# mainBoard.net
KiCad netlist of a schematic drawn in EAGLE
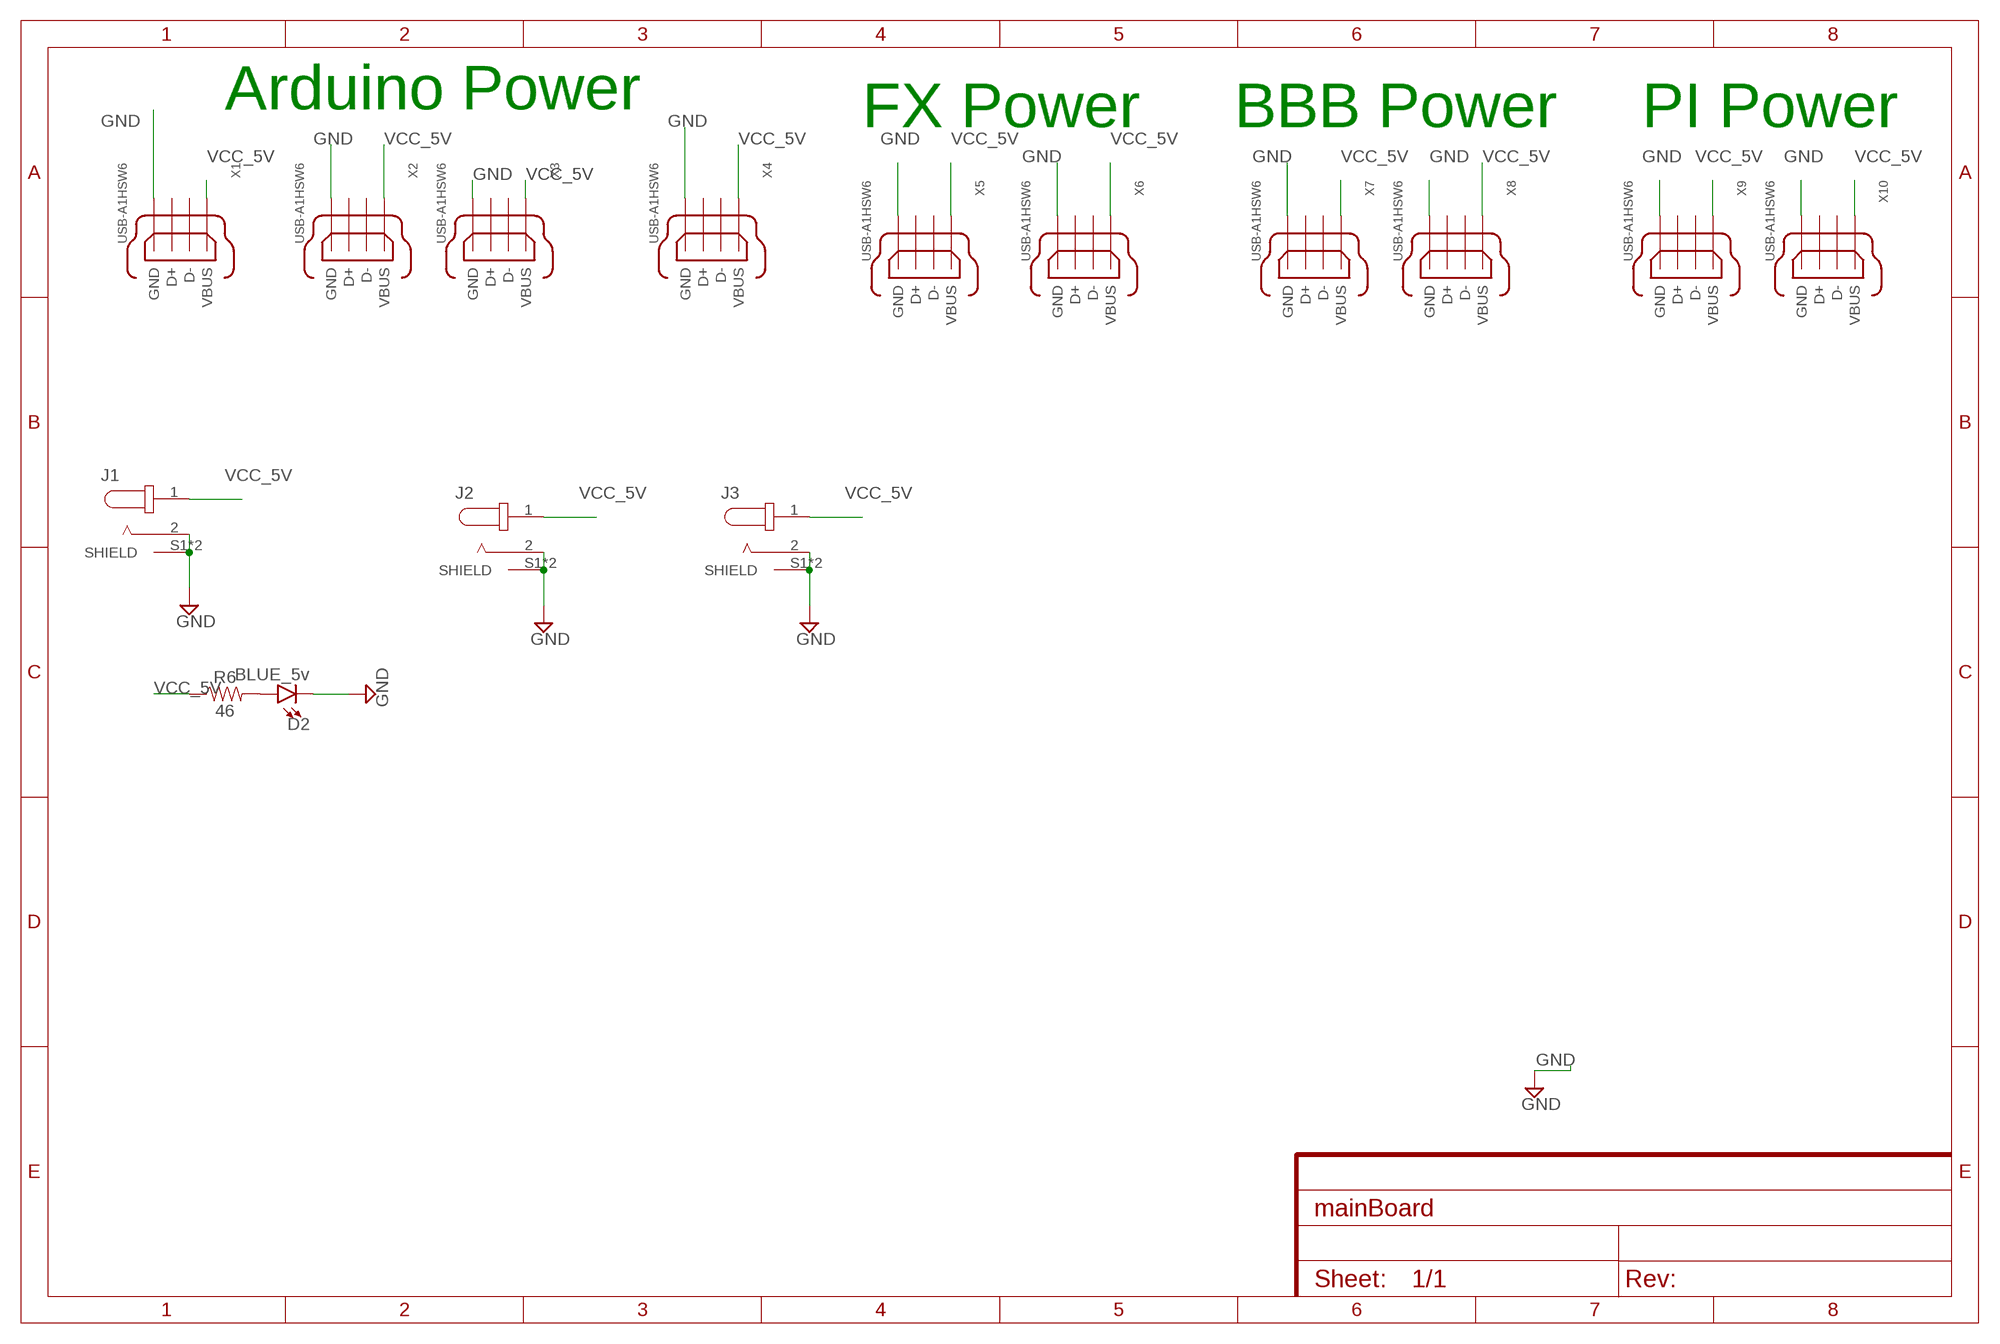
[diagram p0: schematic, sheet 1]

(export (version "E")
  (design (tool "Eeschema 10.0.6"))
  (components
    (comp (ref "D2")
      (value "BLUE_5v")
      (footprint "eagle-import:LED-0603")
      (libsource (lib "eagle-import") (part "LED-BLUE0603"))
    )
    (comp (ref "J1")
      (value "PJ-063AH")
      (footprint "eagle-import:CUI_PJ-063AH")
      (fields (field (name "MF") "CUI Inc."))
      (libsource (lib "eagle-import") (part "PJ-063AH"))
    )
    (comp (ref "J2")
      (value "PJ-063AH")
      (footprint "eagle-import:CUI_PJ-063AH")
      (fields (field (name "MF") "CUI Inc."))
      (libsource (lib "eagle-import") (part "PJ-063AH"))
    )
    (comp (ref "J3")
      (value "PJ-063AH")
      (footprint "eagle-import:CUI_PJ-063AH")
      (fields (field (name "MF") "CUI Inc."))
      (libsource (lib "eagle-import") (part "PJ-063AH"))
    )
    (comp (ref "R6")
      (value "46")
      (footprint "eagle-import:0603")
      (libsource (lib "eagle-import") (part "RESISTOR0603"))
    )
    (comp (ref "X1")
      (value "USB-A1HSW6")
      (footprint "eagle-import:OST_USB-A1HSW6")
      (fields (field (name "MF") "On Shore"))
      (libsource (lib "eagle-import") (part "USB-A1HSW6"))
    )
    (comp (ref "X2")
      (value "USB-A1HSW6")
      (footprint "eagle-import:OST_USB-A1HSW6")
      (fields (field (name "MF") "On Shore"))
      (libsource (lib "eagle-import") (part "USB-A1HSW6"))
    )
    (comp (ref "X3")
      (value "USB-A1HSW6")
      (footprint "eagle-import:OST_USB-A1HSW6")
      (fields (field (name "MF") "On Shore"))
      (libsource (lib "eagle-import") (part "USB-A1HSW6"))
    )
    (comp (ref "X4")
      (value "USB-A1HSW6")
      (footprint "eagle-import:OST_USB-A1HSW6")
      (fields (field (name "MF") "On Shore"))
      (libsource (lib "eagle-import") (part "USB-A1HSW6"))
    )
    (comp (ref "X5")
      (value "USB-A1HSW6")
      (footprint "eagle-import:OST_USB-A1HSW6")
      (fields (field (name "MF") "On Shore"))
      (libsource (lib "eagle-import") (part "USB-A1HSW6"))
    )
    (comp (ref "X6")
      (value "USB-A1HSW6")
      (footprint "eagle-import:OST_USB-A1HSW6")
      (fields (field (name "MF") "On Shore"))
      (libsource (lib "eagle-import") (part "USB-A1HSW6"))
    )
    (comp (ref "X7")
      (value "USB-A1HSW6")
      (footprint "eagle-import:OST_USB-A1HSW6")
      (fields (field (name "MF") "On Shore"))
      (libsource (lib "eagle-import") (part "USB-A1HSW6"))
    )
    (comp (ref "X8")
      (value "USB-A1HSW6")
      (footprint "eagle-import:OST_USB-A1HSW6")
      (fields (field (name "MF") "On Shore"))
      (libsource (lib "eagle-import") (part "USB-A1HSW6"))
    )
    (comp (ref "X9")
      (value "USB-A1HSW6")
      (footprint "eagle-import:OST_USB-A1HSW6")
      (fields (field (name "MF") "On Shore"))
      (libsource (lib "eagle-import") (part "USB-A1HSW6"))
    )
    (comp (ref "X10")
      (value "USB-A1HSW6")
      (footprint "eagle-import:OST_USB-A1HSW6")
      (fields (field (name "MF") "On Shore"))
      (libsource (lib "eagle-import") (part "USB-A1HSW6"))
    )
  )
  (nets
    (net (code "1") (name "/VCC_5V") (class "Default")
      (node (ref "J1") (pin "1") (pinfunction "1_1") (pintype "passive"))
      (node (ref "J2") (pin "1") (pinfunction "1_1") (pintype "passive"))
      (node (ref "J3") (pin "1") (pinfunction "1_1") (pintype "passive"))
      (node (ref "R6") (pin "1") (pinfunction "1_1") (pintype "passive"))
      (node (ref "X1") (pin "1") (pinfunction "VBUS_1") (pintype "power_in"))
      (node (ref "X10") (pin "1") (pinfunction "VBUS_1") (pintype "power_in"))
      (node (ref "X2") (pin "1") (pinfunction "VBUS_1") (pintype "power_in"))
      (node (ref "X3") (pin "1") (pinfunction "VBUS_1") (pintype "power_in"))
      (node (ref "X4") (pin "1") (pinfunction "VBUS_1") (pintype "power_in"))
      (node (ref "X5") (pin "1") (pinfunction "VBUS_1") (pintype "power_in"))
      (node (ref "X6") (pin "1") (pinfunction "VBUS_1") (pintype "power_in"))
      (node (ref "X7") (pin "1") (pinfunction "VBUS_1") (pintype "power_in"))
      (node (ref "X8") (pin "1") (pinfunction "VBUS_1") (pintype "power_in"))
      (node (ref "X9") (pin "1") (pinfunction "VBUS_1") (pintype "power_in"))
    )
    (net (code "2") (name "GND") (class "Default")
      (node (ref "D2") (pin "C") (pinfunction "C_C") (pintype "passive"))
      (node (ref "J1") (pin "2") (pinfunction "2_2") (pintype "passive"))
      (node (ref "J1") (pin "S1") (pinfunction "SHIELD_S1") (pintype "power_in"))
      (node (ref "J1") (pin "S2") (pinfunction "SHIELD_S2") (pintype "power_in"))
      (node (ref "J2") (pin "2") (pinfunction "2_2") (pintype "passive"))
      (node (ref "J2") (pin "S1") (pinfunction "SHIELD_S1") (pintype "power_in"))
      (node (ref "J2") (pin "S2") (pinfunction "SHIELD_S2") (pintype "power_in"))
      (node (ref "J3") (pin "2") (pinfunction "2_2") (pintype "passive"))
      (node (ref "J3") (pin "S1") (pinfunction "SHIELD_S1") (pintype "power_in"))
      (node (ref "J3") (pin "S2") (pinfunction "SHIELD_S2") (pintype "power_in"))
      (node (ref "X1") (pin "4") (pinfunction "GND_4") (pintype "power_in"))
      (node (ref "X10") (pin "4") (pinfunction "GND_4") (pintype "power_in"))
      (node (ref "X2") (pin "4") (pinfunction "GND_4") (pintype "power_in"))
      (node (ref "X3") (pin "4") (pinfunction "GND_4") (pintype "power_in"))
      (node (ref "X4") (pin "4") (pinfunction "GND_4") (pintype "power_in"))
      (node (ref "X5") (pin "4") (pinfunction "GND_4") (pintype "power_in"))
      (node (ref "X6") (pin "4") (pinfunction "GND_4") (pintype "power_in"))
      (node (ref "X7") (pin "4") (pinfunction "GND_4") (pintype "power_in"))
      (node (ref "X8") (pin "4") (pinfunction "GND_4") (pintype "power_in"))
      (node (ref "X9") (pin "4") (pinfunction "GND_4") (pintype "power_in"))
    )
    (net (code "3") (name "Net-(D2-PadA)") (class "Default")
      (node (ref "D2") (pin "A") (pinfunction "A_A") (pintype "passive"))
      (node (ref "R6") (pin "2") (pinfunction "2_2") (pintype "passive"))
    )
    (net (code "4") (name "unconnected-(X1-D+-Pad3)") (class "Default")
      (node (ref "X1") (pin "3") (pinfunction "D+_3") (pintype "bidirectional"))
    )
    (net (code "5") (name "unconnected-(X1-D--Pad2)") (class "Default")
      (node (ref "X1") (pin "2") (pinfunction "D-_2") (pintype "bidirectional"))
    )
    (net (code "6") (name "unconnected-(X2-D+-Pad3)") (class "Default")
      (node (ref "X2") (pin "3") (pinfunction "D+_3") (pintype "bidirectional"))
    )
    (net (code "7") (name "unconnected-(X2-D--Pad2)") (class "Default")
      (node (ref "X2") (pin "2") (pinfunction "D-_2") (pintype "bidirectional"))
    )
    (net (code "8") (name "unconnected-(X3-D+-Pad3)") (class "Default")
      (node (ref "X3") (pin "3") (pinfunction "D+_3") (pintype "bidirectional"))
    )
    (net (code "9") (name "unconnected-(X3-D--Pad2)") (class "Default")
      (node (ref "X3") (pin "2") (pinfunction "D-_2") (pintype "bidirectional"))
    )
    (net (code "10") (name "unconnected-(X4-D+-Pad3)") (class "Default")
      (node (ref "X4") (pin "3") (pinfunction "D+_3") (pintype "bidirectional"))
    )
    (net (code "11") (name "unconnected-(X4-D--Pad2)") (class "Default")
      (node (ref "X4") (pin "2") (pinfunction "D-_2") (pintype "bidirectional"))
    )
    (net (code "12") (name "unconnected-(X5-D+-Pad3)") (class "Default")
      (node (ref "X5") (pin "3") (pinfunction "D+_3") (pintype "bidirectional"))
    )
    (net (code "13") (name "unconnected-(X5-D--Pad2)") (class "Default")
      (node (ref "X5") (pin "2") (pinfunction "D-_2") (pintype "bidirectional"))
    )
    (net (code "14") (name "unconnected-(X6-D+-Pad3)") (class "Default")
      (node (ref "X6") (pin "3") (pinfunction "D+_3") (pintype "bidirectional"))
    )
    (net (code "15") (name "unconnected-(X6-D--Pad2)") (class "Default")
      (node (ref "X6") (pin "2") (pinfunction "D-_2") (pintype "bidirectional"))
    )
    (net (code "16") (name "unconnected-(X7-D+-Pad3)") (class "Default")
      (node (ref "X7") (pin "3") (pinfunction "D+_3") (pintype "bidirectional"))
    )
    (net (code "17") (name "unconnected-(X7-D--Pad2)") (class "Default")
      (node (ref "X7") (pin "2") (pinfunction "D-_2") (pintype "bidirectional"))
    )
    (net (code "18") (name "unconnected-(X8-D+-Pad3)") (class "Default")
      (node (ref "X8") (pin "3") (pinfunction "D+_3") (pintype "bidirectional"))
    )
    (net (code "19") (name "unconnected-(X8-D--Pad2)") (class "Default")
      (node (ref "X8") (pin "2") (pinfunction "D-_2") (pintype "bidirectional"))
    )
    (net (code "20") (name "unconnected-(X9-D+-Pad3)") (class "Default")
      (node (ref "X9") (pin "3") (pinfunction "D+_3") (pintype "bidirectional"))
    )
    (net (code "21") (name "unconnected-(X9-D--Pad2)") (class "Default")
      (node (ref "X9") (pin "2") (pinfunction "D-_2") (pintype "bidirectional"))
    )
    (net (code "22") (name "unconnected-(X10-D+-Pad3)") (class "Default")
      (node (ref "X10") (pin "3") (pinfunction "D+_3") (pintype "bidirectional"))
    )
    (net (code "23") (name "unconnected-(X10-D--Pad2)") (class "Default")
      (node (ref "X10") (pin "2") (pinfunction "D-_2") (pintype "bidirectional"))
    )
  )
)
